# Sensor_Bar_2_0_sensors.net
KiCad netlist of a schematic drawn in Altium Designer
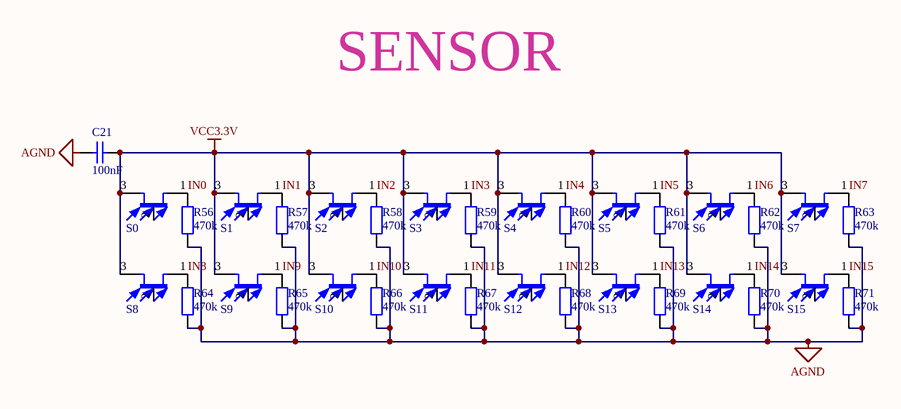
[diagram p0: Sensor Bar 2.0 sensors.SchDoc]

(export (version "E")
  (design (tool "Eeschema 10.0.6"))
  (components
    (comp (ref "C21")
      (value "100nF")
      (footprint "CC2012-0805")
      (description "Capacitor (Semiconductor SIM Model)")
      (fields (field (name "PUBLISHER") "Altium Limited"))
      (libsource (lib "Motorcontrol2.0") (part "Cap Semi"))
    )
    (comp (ref "R56")
      (value "470k")
      (footprint "CR2012-0805")
      (description "Resistor")
      (fields (field (name "PUBLISHER") "Altium Limited"))
      (libsource (lib "Robocon_RCL") (part "Res2"))
    )
    (comp (ref "R57")
      (value "470k")
      (footprint "CR2012-0805")
      (description "Resistor")
      (fields (field (name "PUBLISHER") "Altium Limited"))
      (libsource (lib "Robocon_RCL") (part "Res2"))
    )
    (comp (ref "R58")
      (value "470k")
      (footprint "CR2012-0805")
      (description "Resistor")
      (fields (field (name "PUBLISHER") "Altium Limited"))
      (libsource (lib "Robocon_RCL") (part "Res2"))
    )
    (comp (ref "R59")
      (value "470k")
      (footprint "CR2012-0805")
      (description "Resistor")
      (fields (field (name "PUBLISHER") "Altium Limited"))
      (libsource (lib "Robocon_RCL") (part "Res2"))
    )
    (comp (ref "R60")
      (value "470k")
      (footprint "CR2012-0805")
      (description "Resistor")
      (fields (field (name "PUBLISHER") "Altium Limited"))
      (libsource (lib "Robocon_RCL") (part "Res2"))
    )
    (comp (ref "R61")
      (value "470k")
      (footprint "CR2012-0805")
      (description "Resistor")
      (fields (field (name "PUBLISHER") "Altium Limited"))
      (libsource (lib "Robocon_RCL") (part "Res2"))
    )
    (comp (ref "R62")
      (value "470k")
      (footprint "CR2012-0805")
      (description "Resistor")
      (fields (field (name "PUBLISHER") "Altium Limited"))
      (libsource (lib "Robocon_RCL") (part "Res2"))
    )
    (comp (ref "R63")
      (value "470k")
      (footprint "CR2012-0805")
      (description "Resistor")
      (fields (field (name "PUBLISHER") "Altium Limited"))
      (libsource (lib "Robocon_RCL") (part "Res2"))
    )
    (comp (ref "R64")
      (value "470k")
      (footprint "CR2012-0805")
      (description "Resistor")
      (fields (field (name "PUBLISHER") "Altium Limited"))
      (libsource (lib "Robocon_RCL") (part "Res2"))
    )
    (comp (ref "R65")
      (value "470k")
      (footprint "CR2012-0805")
      (description "Resistor")
      (fields (field (name "PUBLISHER") "Altium Limited"))
      (libsource (lib "Robocon_RCL") (part "Res2"))
    )
    (comp (ref "R66")
      (value "470k")
      (footprint "CR2012-0805")
      (description "Resistor")
      (fields (field (name "PUBLISHER") "Altium Limited"))
      (libsource (lib "Robocon_RCL") (part "Res2"))
    )
    (comp (ref "R67")
      (value "470k")
      (footprint "CR2012-0805")
      (description "Resistor")
      (fields (field (name "PUBLISHER") "Altium Limited"))
      (libsource (lib "Robocon_RCL") (part "Res2"))
    )
    (comp (ref "R68")
      (value "470k")
      (footprint "CR2012-0805")
      (description "Resistor")
      (fields (field (name "PUBLISHER") "Altium Limited"))
      (libsource (lib "Robocon_RCL") (part "Res2"))
    )
    (comp (ref "R69")
      (value "470k")
      (footprint "CR2012-0805")
      (description "Resistor")
      (fields (field (name "PUBLISHER") "Altium Limited"))
      (libsource (lib "Robocon_RCL") (part "Res2"))
    )
    (comp (ref "R70")
      (value "470k")
      (footprint "CR2012-0805")
      (description "Resistor")
      (fields (field (name "PUBLISHER") "Altium Limited"))
      (libsource (lib "Robocon_RCL") (part "Res2"))
    )
    (comp (ref "R71")
      (value "470k")
      (footprint "CR2012-0805")
      (description "Resistor")
      (fields (field (name "PUBLISHER") "Altium Limited"))
      (libsource (lib "Robocon_RCL") (part "Res2"))
    )
    (comp (ref "S0")
      (value "3du5c")
      (footprint "CAN-3/D5.9")
      (libsource (lib "BJT_MOS_DIODE(2009)") (part "Light"))
    )
    (comp (ref "S1")
      (value "3du5c")
      (footprint "CAN-3/D5.9")
      (libsource (lib "BJT_MOS_DIODE(2009)") (part "Light"))
    )
    (comp (ref "S2")
      (value "3du5c")
      (footprint "CAN-3/D5.9")
      (libsource (lib "BJT_MOS_DIODE(2009)") (part "Light"))
    )
    (comp (ref "S3")
      (value "3du5c")
      (footprint "CAN-3/D5.9")
      (libsource (lib "BJT_MOS_DIODE(2009)") (part "Light"))
    )
    (comp (ref "S4")
      (value "3du5c")
      (footprint "CAN-3/D5.9")
      (libsource (lib "BJT_MOS_DIODE(2009)") (part "Light"))
    )
    (comp (ref "S5")
      (value "3du5c")
      (footprint "CAN-3/D5.9")
      (libsource (lib "BJT_MOS_DIODE(2009)") (part "Light"))
    )
    (comp (ref "S6")
      (value "3du5c")
      (footprint "CAN-3/D5.9")
      (libsource (lib "BJT_MOS_DIODE(2009)") (part "Light"))
    )
    (comp (ref "S7")
      (value "3du5c")
      (footprint "CAN-3/D5.9")
      (libsource (lib "BJT_MOS_DIODE(2009)") (part "Light"))
    )
    (comp (ref "S8")
      (value "3du5c")
      (footprint "CAN-3/D5.9")
      (libsource (lib "BJT_MOS_DIODE(2009)") (part "Light"))
    )
    (comp (ref "S9")
      (value "3du5c")
      (footprint "CAN-3/D5.9")
      (libsource (lib "BJT_MOS_DIODE(2009)") (part "Light"))
    )
    (comp (ref "S10")
      (value "3du5c")
      (footprint "CAN-3/D5.9")
      (libsource (lib "BJT_MOS_DIODE(2009)") (part "Light"))
    )
    (comp (ref "S11")
      (value "3du5c")
      (footprint "CAN-3/D5.9")
      (libsource (lib "BJT_MOS_DIODE(2009)") (part "Light"))
    )
    (comp (ref "S12")
      (value "3du5c")
      (footprint "CAN-3/D5.9")
      (libsource (lib "BJT_MOS_DIODE(2009)") (part "Light"))
    )
    (comp (ref "S13")
      (value "3du5c")
      (footprint "CAN-3/D5.9")
      (libsource (lib "BJT_MOS_DIODE(2009)") (part "Light"))
    )
    (comp (ref "S14")
      (value "3du5c")
      (footprint "CAN-3/D5.9")
      (libsource (lib "BJT_MOS_DIODE(2009)") (part "Light"))
    )
    (comp (ref "S15")
      (value "3du5c")
      (footprint "CAN-3/D5.9")
      (libsource (lib "BJT_MOS_DIODE(2009)") (part "Light"))
    )
  )
  (nets
    (net (code "1") (name "/IN0") (class "Default")
      (node (ref "R56") (pin "2") (pinfunction "2_2") (pintype "passive"))
      (node (ref "S0") (pin "1") (pintype "passive"))
    )
    (net (code "2") (name "/IN1") (class "Default")
      (node (ref "R57") (pin "2") (pinfunction "2_2") (pintype "passive"))
      (node (ref "S1") (pin "1") (pintype "passive"))
    )
    (net (code "3") (name "/IN2") (class "Default")
      (node (ref "R58") (pin "2") (pinfunction "2_2") (pintype "passive"))
      (node (ref "S2") (pin "1") (pintype "passive"))
    )
    (net (code "4") (name "/IN3") (class "Default")
      (node (ref "R59") (pin "2") (pinfunction "2_2") (pintype "passive"))
      (node (ref "S3") (pin "1") (pintype "passive"))
    )
    (net (code "5") (name "/IN4") (class "Default")
      (node (ref "R60") (pin "2") (pinfunction "2_2") (pintype "passive"))
      (node (ref "S4") (pin "1") (pintype "passive"))
    )
    (net (code "6") (name "/IN5") (class "Default")
      (node (ref "R61") (pin "2") (pinfunction "2_2") (pintype "passive"))
      (node (ref "S5") (pin "1") (pintype "passive"))
    )
    (net (code "7") (name "/IN6") (class "Default")
      (node (ref "R62") (pin "2") (pinfunction "2_2") (pintype "passive"))
      (node (ref "S6") (pin "1") (pintype "passive"))
    )
    (net (code "8") (name "/IN7") (class "Default")
      (node (ref "R63") (pin "2") (pinfunction "2_2") (pintype "passive"))
      (node (ref "S7") (pin "1") (pintype "passive"))
    )
    (net (code "9") (name "/IN8") (class "Default")
      (node (ref "R64") (pin "2") (pinfunction "2_2") (pintype "passive"))
      (node (ref "S8") (pin "1") (pintype "passive"))
    )
    (net (code "10") (name "/IN9") (class "Default")
      (node (ref "R65") (pin "2") (pinfunction "2_2") (pintype "passive"))
      (node (ref "S9") (pin "1") (pintype "passive"))
    )
    (net (code "11") (name "/IN10") (class "Default")
      (node (ref "R66") (pin "2") (pinfunction "2_2") (pintype "passive"))
      (node (ref "S10") (pin "1") (pintype "passive"))
    )
    (net (code "12") (name "/IN11") (class "Default")
      (node (ref "R67") (pin "2") (pinfunction "2_2") (pintype "passive"))
      (node (ref "S11") (pin "1") (pintype "passive"))
    )
    (net (code "13") (name "/IN12") (class "Default")
      (node (ref "R68") (pin "2") (pinfunction "2_2") (pintype "passive"))
      (node (ref "S12") (pin "1") (pintype "passive"))
    )
    (net (code "14") (name "/IN13") (class "Default")
      (node (ref "R69") (pin "2") (pinfunction "2_2") (pintype "passive"))
      (node (ref "S13") (pin "1") (pintype "passive"))
    )
    (net (code "15") (name "/IN14") (class "Default")
      (node (ref "R70") (pin "2") (pinfunction "2_2") (pintype "passive"))
      (node (ref "S14") (pin "1") (pintype "passive"))
    )
    (net (code "16") (name "/IN15") (class "Default")
      (node (ref "R71") (pin "2") (pinfunction "2_2") (pintype "passive"))
      (node (ref "S15") (pin "1") (pintype "passive"))
    )
    (net (code "17") (name "AGND") (class "Default")
      (node (ref "C21") (pin "2") (pinfunction "2_2") (pintype "passive"))
      (node (ref "R56") (pin "1") (pinfunction "1_1") (pintype "passive"))
      (node (ref "R57") (pin "1") (pinfunction "1_1") (pintype "passive"))
      (node (ref "R58") (pin "1") (pinfunction "1_1") (pintype "passive"))
      (node (ref "R59") (pin "1") (pinfunction "1_1") (pintype "passive"))
      (node (ref "R60") (pin "1") (pinfunction "1_1") (pintype "passive"))
      (node (ref "R61") (pin "1") (pinfunction "1_1") (pintype "passive"))
      (node (ref "R62") (pin "1") (pinfunction "1_1") (pintype "passive"))
      (node (ref "R63") (pin "1") (pinfunction "1_1") (pintype "passive"))
      (node (ref "R64") (pin "1") (pinfunction "1_1") (pintype "passive"))
      (node (ref "R65") (pin "1") (pinfunction "1_1") (pintype "passive"))
      (node (ref "R66") (pin "1") (pinfunction "1_1") (pintype "passive"))
      (node (ref "R67") (pin "1") (pinfunction "1_1") (pintype "passive"))
      (node (ref "R68") (pin "1") (pinfunction "1_1") (pintype "passive"))
      (node (ref "R69") (pin "1") (pinfunction "1_1") (pintype "passive"))
      (node (ref "R70") (pin "1") (pinfunction "1_1") (pintype "passive"))
      (node (ref "R71") (pin "1") (pinfunction "1_1") (pintype "passive"))
    )
    (net (code "18") (name "VCC3.3V") (class "Default")
      (node (ref "C21") (pin "1") (pinfunction "1_1") (pintype "passive"))
      (node (ref "S0") (pin "3") (pintype "passive"))
      (node (ref "S1") (pin "3") (pintype "passive"))
      (node (ref "S10") (pin "3") (pintype "passive"))
      (node (ref "S11") (pin "3") (pintype "passive"))
      (node (ref "S12") (pin "3") (pintype "passive"))
      (node (ref "S13") (pin "3") (pintype "passive"))
      (node (ref "S14") (pin "3") (pintype "passive"))
      (node (ref "S15") (pin "3") (pintype "passive"))
      (node (ref "S2") (pin "3") (pintype "passive"))
      (node (ref "S3") (pin "3") (pintype "passive"))
      (node (ref "S4") (pin "3") (pintype "passive"))
      (node (ref "S5") (pin "3") (pintype "passive"))
      (node (ref "S6") (pin "3") (pintype "passive"))
      (node (ref "S7") (pin "3") (pintype "passive"))
      (node (ref "S8") (pin "3") (pintype "passive"))
      (node (ref "S9") (pin "3") (pintype "passive"))
    )
    (net (code "19") (name "unconnected-(S0-Pad2)") (class "Default")
      (node (ref "S0") (pin "2") (pintype "passive"))
    )
    (net (code "20") (name "unconnected-(S1-Pad2)") (class "Default")
      (node (ref "S1") (pin "2") (pintype "passive"))
    )
    (net (code "21") (name "unconnected-(S2-Pad2)") (class "Default")
      (node (ref "S2") (pin "2") (pintype "passive"))
    )
    (net (code "22") (name "unconnected-(S3-Pad2)") (class "Default")
      (node (ref "S3") (pin "2") (pintype "passive"))
    )
    (net (code "23") (name "unconnected-(S4-Pad2)") (class "Default")
      (node (ref "S4") (pin "2") (pintype "passive"))
    )
    (net (code "24") (name "unconnected-(S5-Pad2)") (class "Default")
      (node (ref "S5") (pin "2") (pintype "passive"))
    )
    (net (code "25") (name "unconnected-(S6-Pad2)") (class "Default")
      (node (ref "S6") (pin "2") (pintype "passive"))
    )
    (net (code "26") (name "unconnected-(S7-Pad2)") (class "Default")
      (node (ref "S7") (pin "2") (pintype "passive"))
    )
    (net (code "27") (name "unconnected-(S8-Pad2)") (class "Default")
      (node (ref "S8") (pin "2") (pintype "passive"))
    )
    (net (code "28") (name "unconnected-(S9-Pad2)") (class "Default")
      (node (ref "S9") (pin "2") (pintype "passive"))
    )
    (net (code "29") (name "unconnected-(S10-Pad2)") (class "Default")
      (node (ref "S10") (pin "2") (pintype "passive"))
    )
    (net (code "30") (name "unconnected-(S11-Pad2)") (class "Default")
      (node (ref "S11") (pin "2") (pintype "passive"))
    )
    (net (code "31") (name "unconnected-(S12-Pad2)") (class "Default")
      (node (ref "S12") (pin "2") (pintype "passive"))
    )
    (net (code "32") (name "unconnected-(S13-Pad2)") (class "Default")
      (node (ref "S13") (pin "2") (pintype "passive"))
    )
    (net (code "33") (name "unconnected-(S14-Pad2)") (class "Default")
      (node (ref "S14") (pin "2") (pintype "passive"))
    )
    (net (code "34") (name "unconnected-(S15-Pad2)") (class "Default")
      (node (ref "S15") (pin "2") (pintype "passive"))
    )
  )
)
